# SmartBinDiagram.net
KiCad netlist of a schematic drawn in EasyEDA
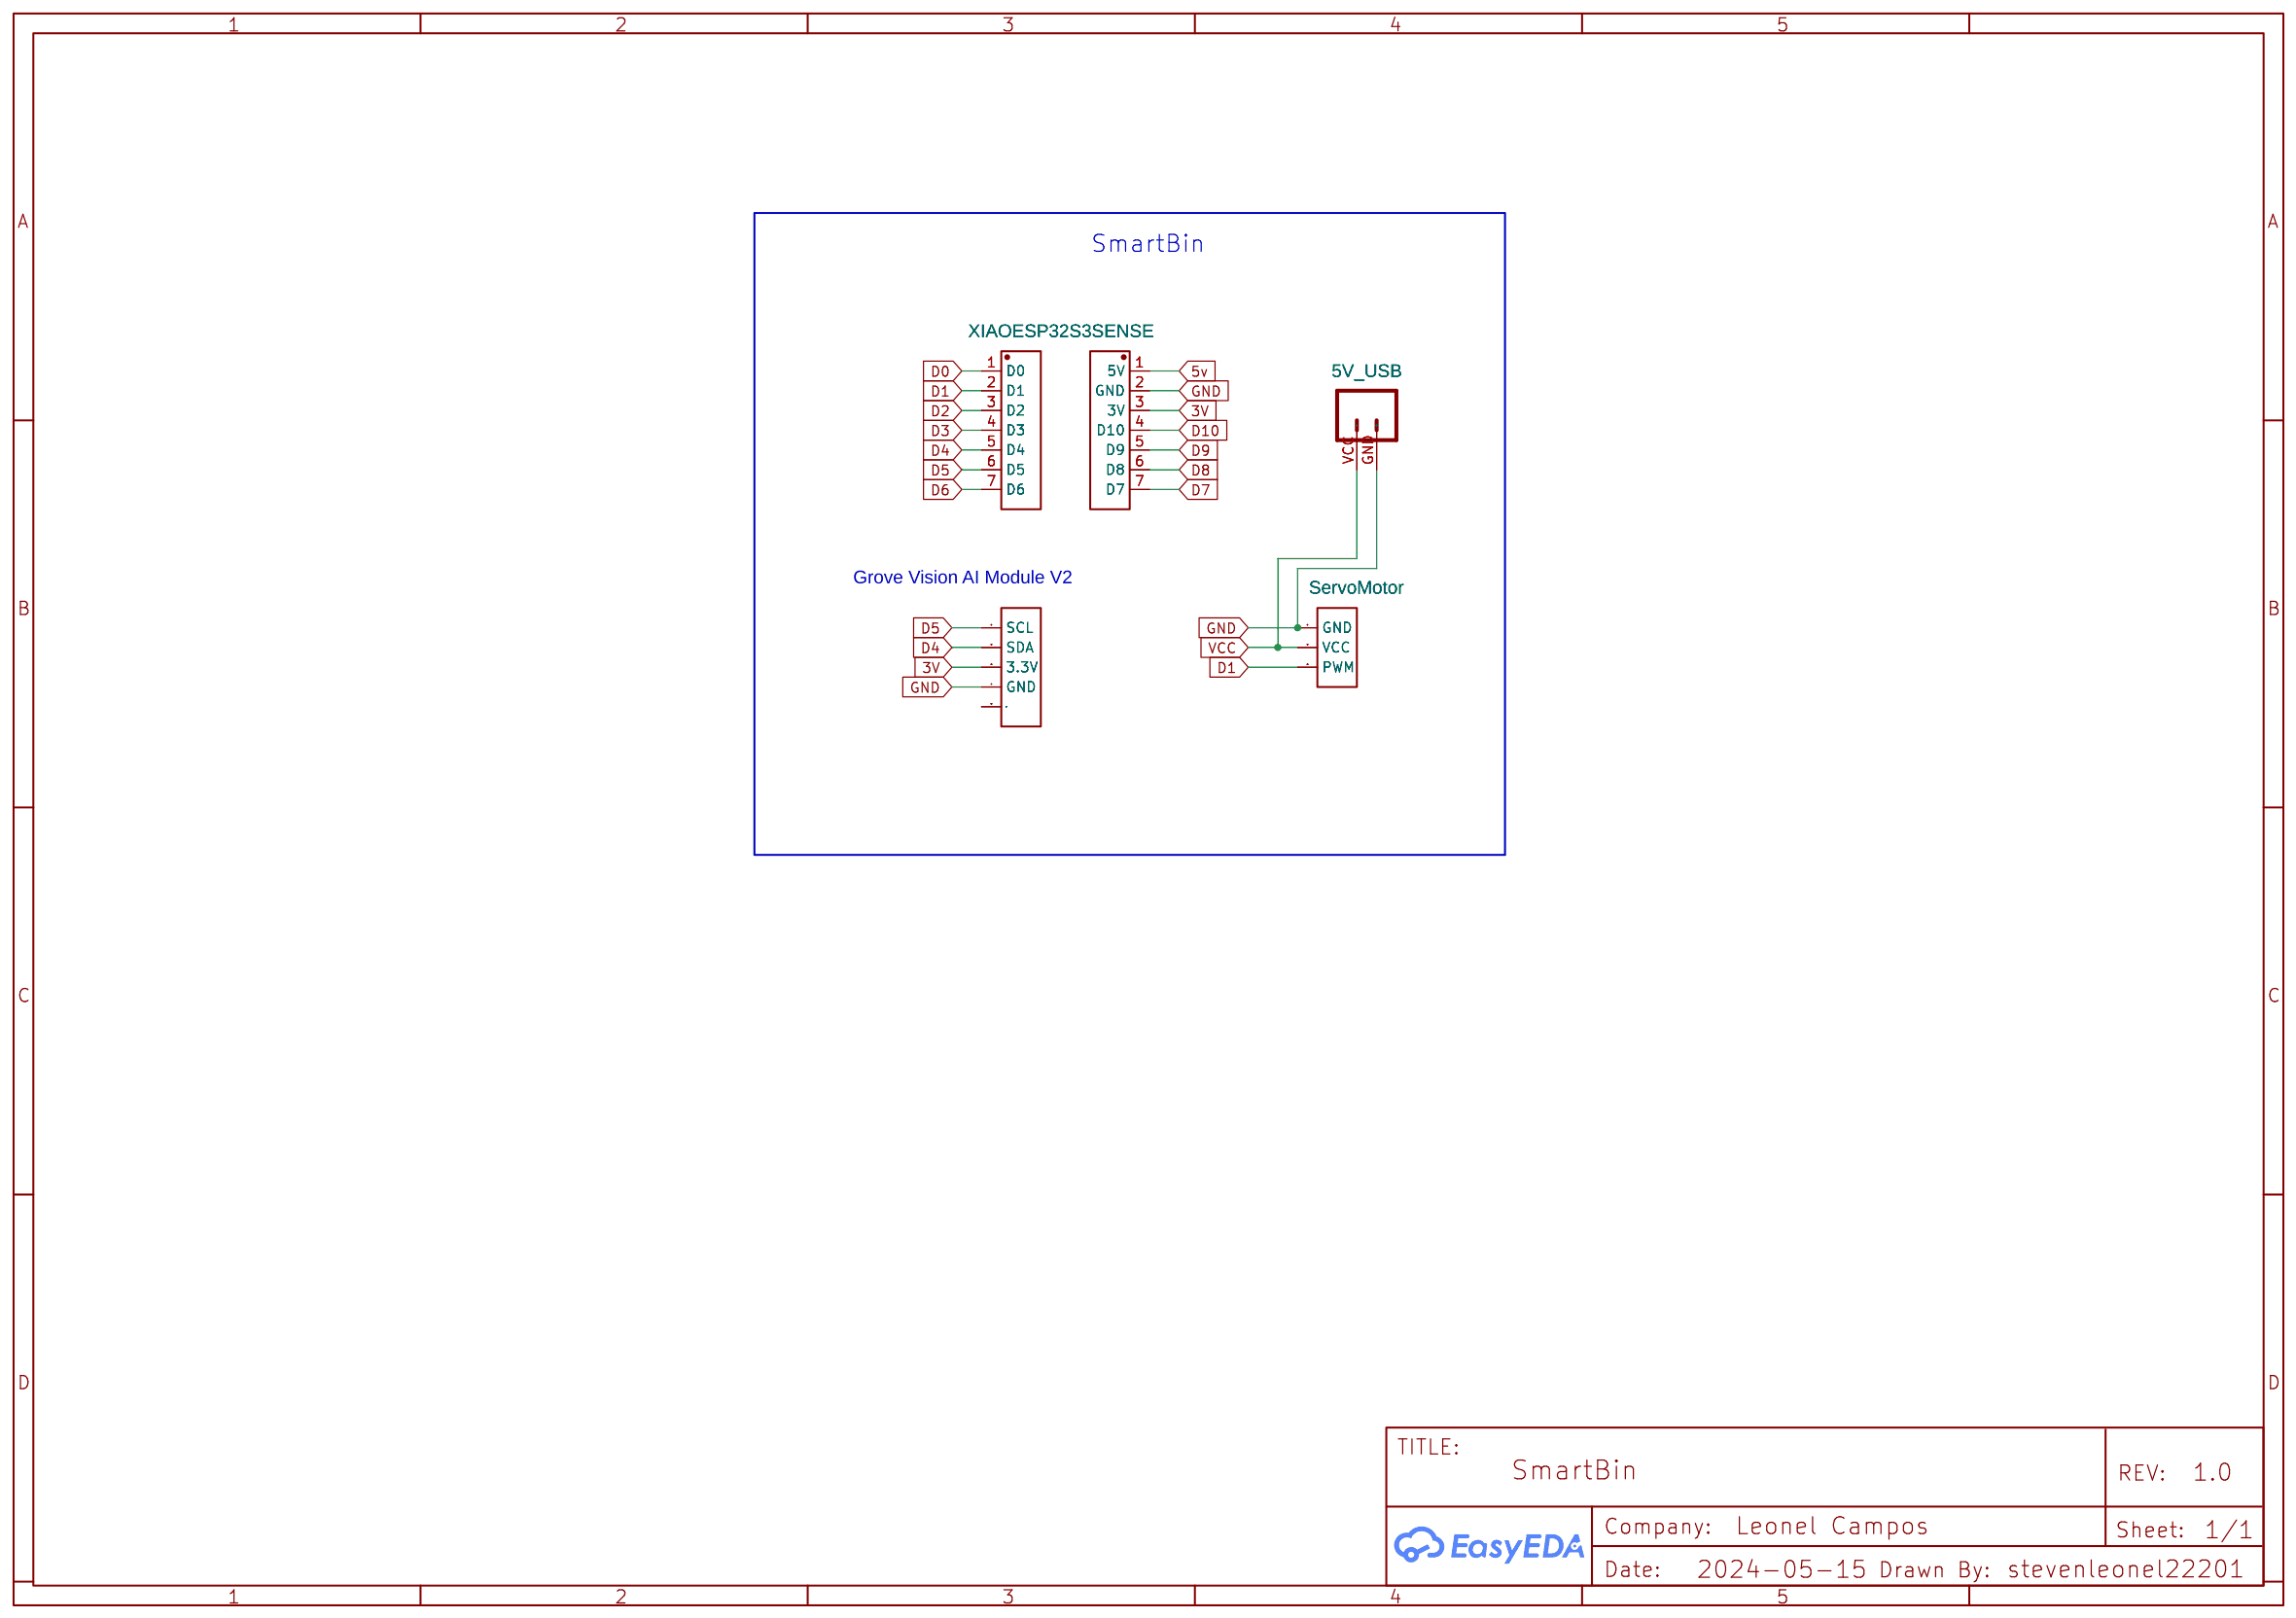
[diagram p0: schematic sheet]

(export (version "E")
  (design (tool "Eeschema 10.0.6"))
  (components
    (comp (ref "5V_USB") (value "NO") (libsource (lib "") (part "M025MM")))
    (comp (ref "G1")
      (value "Header-Female-2.54_1x5")
      (fields (field (name "Manufacturer Part") "2.54-1*5P母") (field (name "Manufacturer") "BOOMELE(博穆精密)"))
      (libsource (lib "") (part "Header-Female-2.54_1x5"))
    )
    (comp (ref "P2")
      (value "ServoMotor")
      (fields (field (name "Manufacturer Part") "2.54-1*3P母") (field (name "Manufacturer") "BOOMELE(博穆精密)"))
      (libsource (lib "") (part "Header-Female-2.54_1x3"))
    )
    (comp (ref "XIAOESP32S3SENSE")
      (value "PIN HEADER - 1X7")
      (libsource (lib "") (part "PIN HEADER - 1X7_1"))
    )
    (comp (ref "XIAOL1") (value "PIN HEADER - 1X7") (libsource (lib "") (part "PIN HEADER - 1X7")))
  )
  (nets
    (net (code "1") (name "3V") (class "Default")
      (node (ref "G1") (pin "3") (pinfunction "3.3V_3") (pintype "input"))
      (node (ref "XIAOESP32S3SENSE") (pin "3") (pinfunction "3V_3") (pintype "unspecified"))
    )
    (net (code "2") (name "5v") (class "Default")
      (node (ref "XIAOESP32S3SENSE") (pin "1") (pinfunction "5V_1") (pintype "unspecified"))
    )
    (net (code "3") (name "D0") (class "Default")
      (node (ref "XIAOL1") (pin "1") (pinfunction "D0_1") (pintype "unspecified"))
    )
    (net (code "4") (name "D1") (class "Default")
      (node (ref "P2") (pin "3") (pinfunction "PWM_3") (pintype "input"))
      (node (ref "XIAOL1") (pin "2") (pinfunction "D1_2") (pintype "unspecified"))
    )
    (net (code "5") (name "D2") (class "Default")
      (node (ref "XIAOL1") (pin "3") (pinfunction "D2_3") (pintype "unspecified"))
    )
    (net (code "6") (name "D3") (class "Default")
      (node (ref "XIAOL1") (pin "4") (pinfunction "D3_4") (pintype "unspecified"))
    )
    (net (code "7") (name "D4") (class "Default")
      (node (ref "G1") (pin "2") (pinfunction "SDA_2") (pintype "input"))
      (node (ref "XIAOL1") (pin "5") (pinfunction "D4_5") (pintype "unspecified"))
    )
    (net (code "8") (name "D5") (class "Default")
      (node (ref "G1") (pin "1") (pinfunction "SCL_1") (pintype "input"))
      (node (ref "XIAOL1") (pin "6") (pinfunction "D5_6") (pintype "unspecified"))
    )
    (net (code "9") (name "D6") (class "Default")
      (node (ref "XIAOL1") (pin "7") (pinfunction "D6_7") (pintype "unspecified"))
    )
    (net (code "10") (name "D7") (class "Default")
      (node (ref "XIAOESP32S3SENSE") (pin "7") (pinfunction "D7_7") (pintype "unspecified"))
    )
    (net (code "11") (name "D8") (class "Default")
      (node (ref "XIAOESP32S3SENSE") (pin "6") (pinfunction "D8_6") (pintype "unspecified"))
    )
    (net (code "12") (name "D9") (class "Default")
      (node (ref "XIAOESP32S3SENSE") (pin "5") (pinfunction "D9_5") (pintype "unspecified"))
    )
    (net (code "13") (name "D10") (class "Default")
      (node (ref "XIAOESP32S3SENSE") (pin "4") (pinfunction "D10_4") (pintype "unspecified"))
    )
    (net (code "14") (name "GND") (class "Default")
      (node (ref "5V_USB") (pin "GND") (pinfunction "2_GND") (pintype "unspecified"))
      (node (ref "G1") (pin "4") (pinfunction "GND_4") (pintype "input"))
      (node (ref "P2") (pin "1") (pinfunction "GND_1") (pintype "input"))
      (node (ref "XIAOESP32S3SENSE") (pin "2") (pinfunction "GND_2") (pintype "unspecified"))
    )
    (net (code "15") (name "VCC") (class "Default")
      (node (ref "5V_USB") (pin "VCC") (pinfunction "1_VCC") (pintype "unspecified"))
      (node (ref "P2") (pin "2") (pinfunction "VCC_2") (pintype "input"))
    )
    (net (code "16") (name "unconnected-(G1-Pad5)") (class "Default")
      (node (ref "G1") (pin "5") (pinfunction "5_5") (pintype "input"))
    )
  )
)
